# DC-DC_SY8120B1.net
KiCad netlist of a schematic drawn in Altium Designer
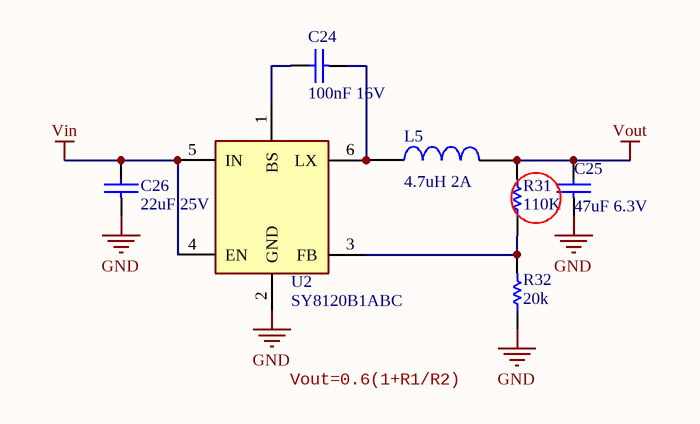
[diagram p0: DC-DC SY8120B1.SchDoc]

(export (version "E")
  (design (tool "Eeschema 10.0.6"))
  (components
    (comp (ref "C24") (value "100nF 16V") (footprint "电容:0402C") (libsource (lib "电容") (part "CAP-NP")))
    (comp (ref "C25") (value "47uF 6.3V") (footprint "电容:0805C") (libsource (lib "电容") (part "CAP-NP")))
    (comp (ref "C26")
      (value "22uF 25V")
      (footprint "电容:0805C")
      (description "22uF (226) ±20% 25V X5R")
      (libsource (lib "电容") (part "CAP-NP"))
    )
    (comp (ref "L5")
      (value "4.7uH 2A")
      (footprint "CD32")
      (description "INDUCTOR")
      (libsource (lib "电感") (part "INDUCTOR"))
    )
    (comp (ref "R31")
      (value "110K")
      (footprint "[01]PCB_ComputerVision2:0402R")
      (libsource (lib "电阻") (part "RES"))
    )
    (comp (ref "R32")
      (value "20k")
      (footprint "[01]PCB_ComputerVision2:0402R")
      (libsource (lib "电阻") (part "RES"))
    )
    (comp (ref "U2")
      (value "SY8120B1ABC")
      (footprint "SOT23-6")
      (fields (field (name "MANUFACTURER_PART_NUMBER") "SY8088AAC"))
      (libsource (lib "电源芯片") (part "SY8120B1ABC"))
    )
  )
  (nets
    (net (code "1") (name "GND") (class "Default")
      (node (ref "C25") (pin "1") (pinfunction "1_1") (pintype "passive"))
      (node (ref "C26") (pin "1") (pinfunction "1_1") (pintype "passive"))
      (node (ref "R32") (pin "1") (pinfunction "1_1") (pintype "passive"))
      (node (ref "U2") (pin "2") (pinfunction "GND_2") (pintype "passive"))
    )
    (net (code "2") (name "Net-(U2-BS)") (class "Default")
      (node (ref "C24") (pin "2") (pinfunction "2_2") (pintype "passive"))
      (node (ref "U2") (pin "1") (pinfunction "BS_1") (pintype "passive"))
    )
    (net (code "3") (name "Net-(U2-FB)") (class "Default")
      (node (ref "R31") (pin "1") (pinfunction "1_1") (pintype "passive"))
      (node (ref "R32") (pin "2") (pinfunction "2_2") (pintype "passive"))
      (node (ref "U2") (pin "3") (pinfunction "FB_3") (pintype "passive"))
    )
    (net (code "4") (name "Net-(U2-LX)") (class "Default")
      (node (ref "C24") (pin "1") (pinfunction "1_1") (pintype "passive"))
      (node (ref "L5") (pin "1") (pinfunction "1_1") (pintype "passive"))
      (node (ref "U2") (pin "6") (pinfunction "LX_6") (pintype "passive"))
    )
    (net (code "5") (name "Vin") (class "Default")
      (node (ref "C26") (pin "2") (pinfunction "2_2") (pintype "passive"))
      (node (ref "U2") (pin "4") (pinfunction "EN_4") (pintype "passive"))
      (node (ref "U2") (pin "5") (pinfunction "IN_5") (pintype "passive"))
    )
    (net (code "6") (name "Vout") (class "Default")
      (node (ref "C25") (pin "2") (pinfunction "2_2") (pintype "passive"))
      (node (ref "L5") (pin "2") (pinfunction "2_2") (pintype "passive"))
      (node (ref "R31") (pin "2") (pinfunction "2_2") (pintype "passive"))
    )
  )
)
